# RasPiHAT-INPUT.net
KiCad netlist of a schematic drawn in Altium Designer
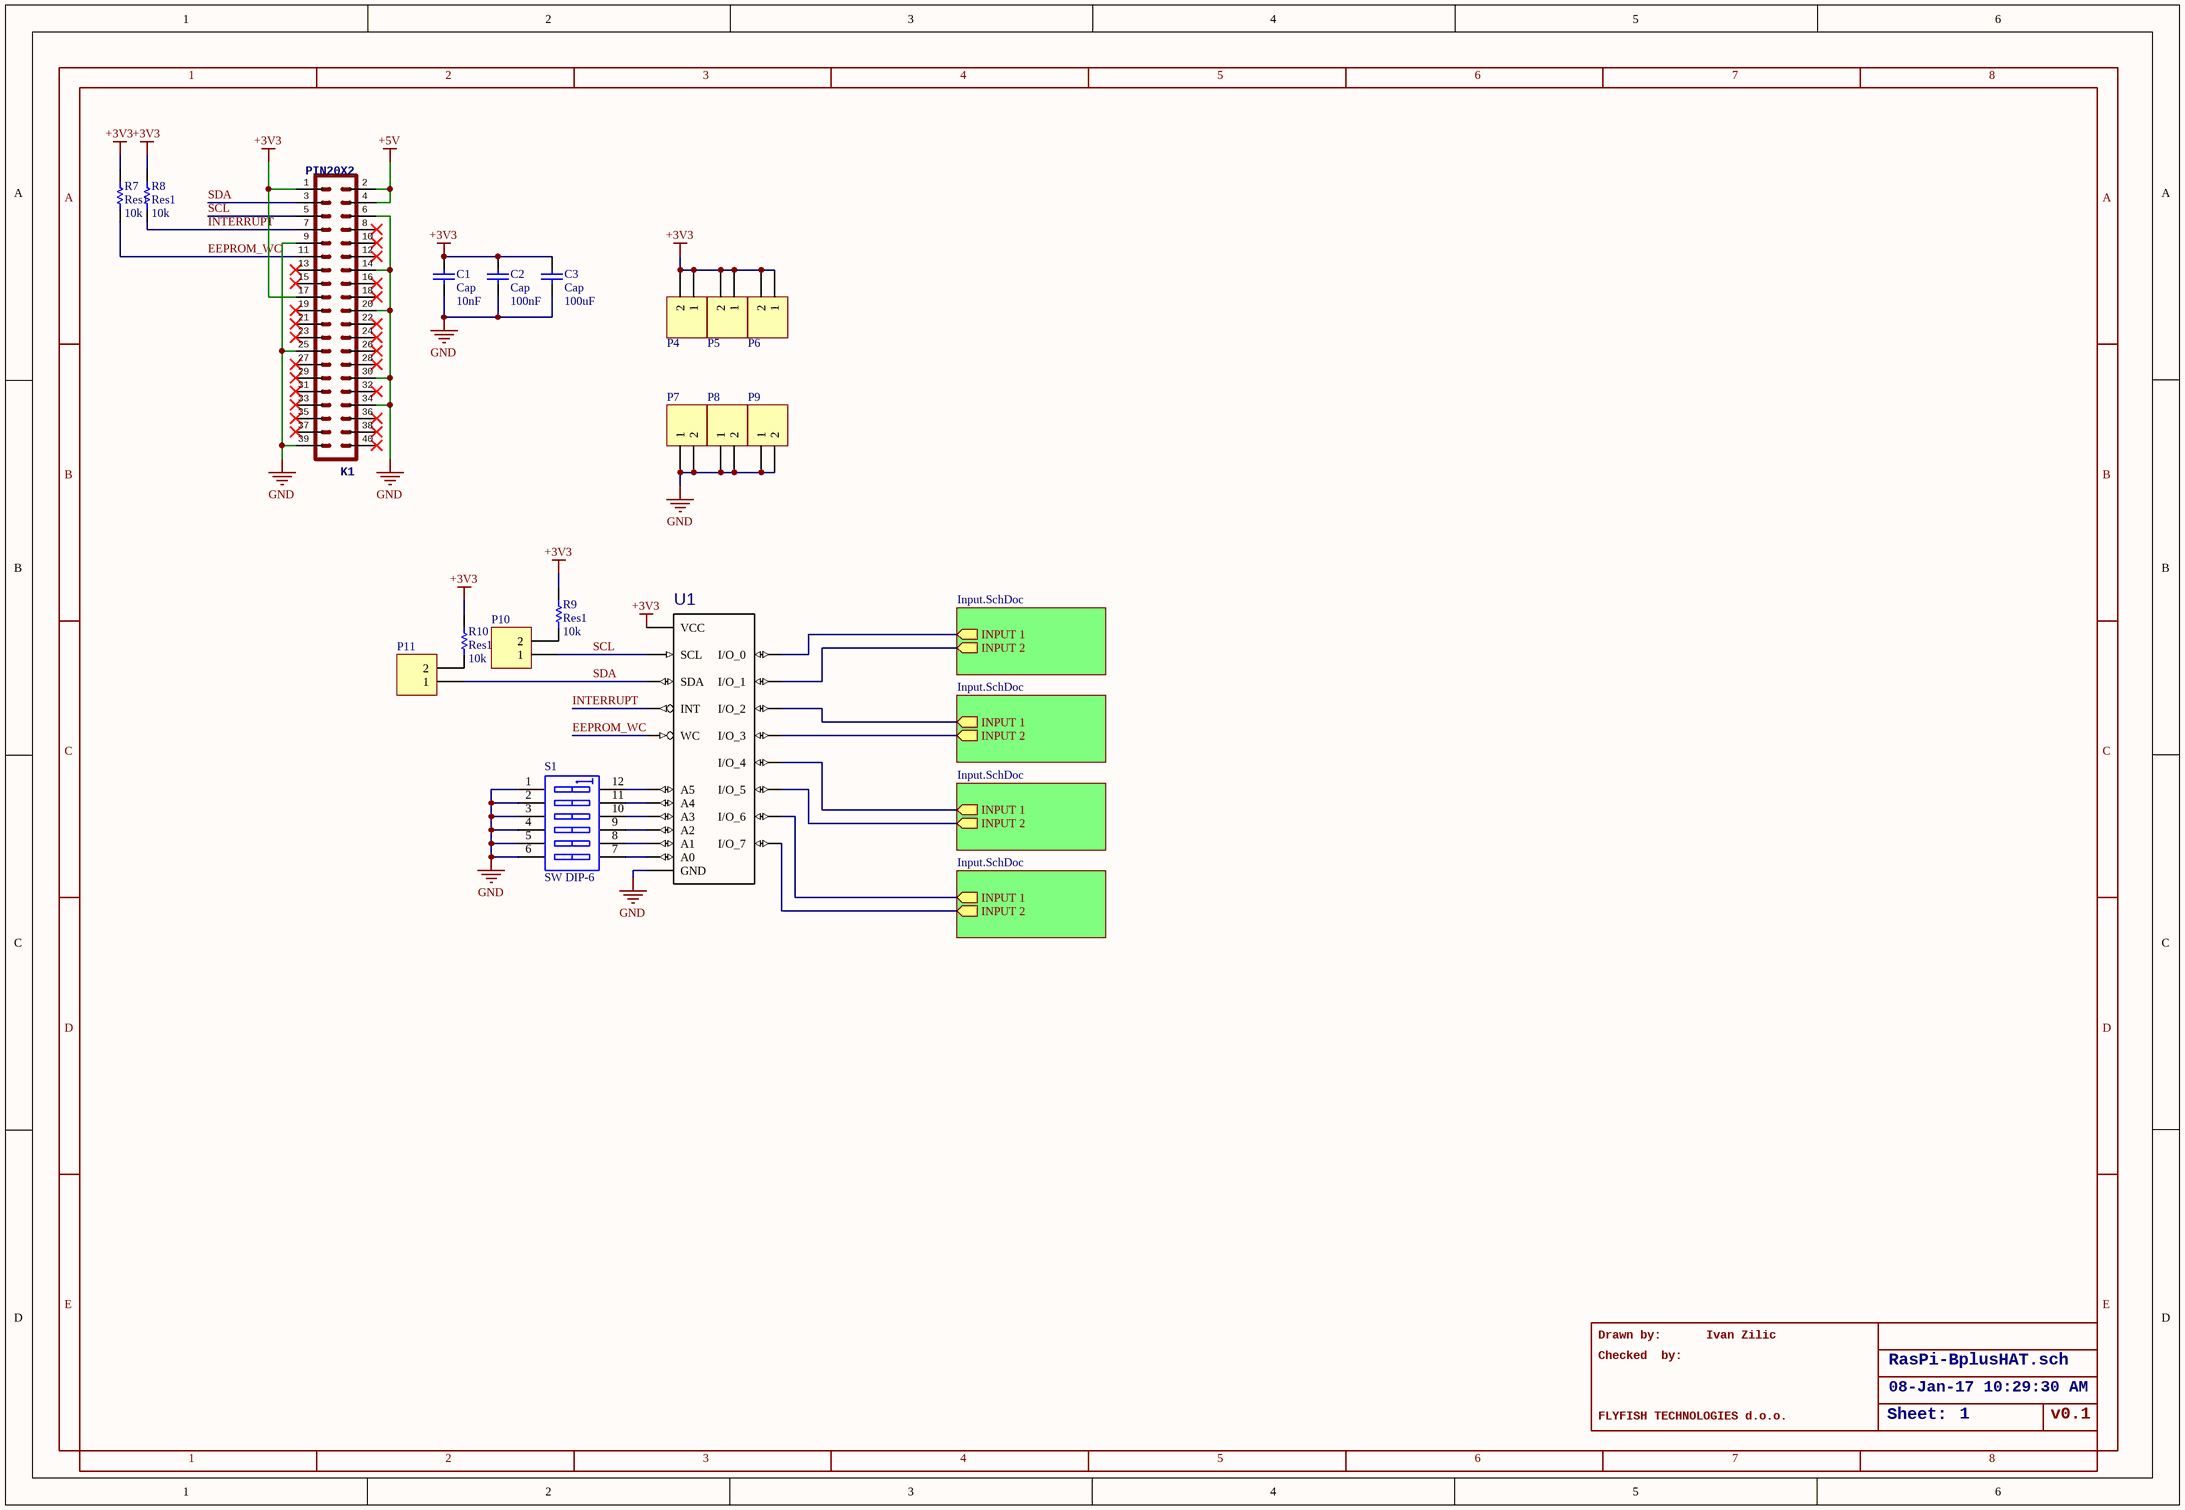
[diagram p0: RasPiHAT-INPUT.SchDoc]

(export (version "E")
  (design (tool "Eeschema 10.0.6"))
  (components
    (comp (ref "C1")
      (value "Cap")
      (footprint "6-0805_N")
      (description "Capacitor")
      (fields (field (name "ALTIUM_VALUE") "10nF") (field (name "PUBLISHER") "Altium Limited"))
      (libsource (lib "Miscellaneous Devices") (part "Cap"))
    )
    (comp (ref "C2")
      (value "Cap")
      (footprint "6-0805_N")
      (description "Capacitor")
      (fields (field (name "ALTIUM_VALUE") "100nF") (field (name "PUBLISHER") "Altium Limited"))
      (libsource (lib "Miscellaneous Devices") (part "Cap"))
    )
    (comp (ref "C3")
      (value "Cap")
      (footprint "6-0805_N")
      (description "Capacitor")
      (fields (field (name "ALTIUM_VALUE") "100uF") (field (name "PUBLISHER") "Altium Limited"))
      (libsource (lib "Miscellaneous Devices") (part "Cap"))
    )
    (comp (ref "K1")
      (value "PIN20X2")
      (footprint "HDR2X20")
      (fields (field (name ">VALUE") "PIN20X2") (field (name ">NAME") "K1"))
      (libsource (lib "FLYFISH") (part "PIN20X2"))
    )
    (comp (ref "P4")
      (value "Header 2")
      (footprint "2 PIN TERM BLK")
      (description "Header, 2-Pin")
      (fields (field (name "PUBLISHER") "Altium Limited"))
      (libsource (lib "") (part "Header 2_1"))
    )
    (comp (ref "P5")
      (value "Header 2")
      (footprint "2 PIN TERM BLK")
      (description "Header, 2-Pin")
      (fields (field (name "PUBLISHER") "Altium Limited"))
      (libsource (lib "") (part "Header 2_1"))
    )
    (comp (ref "P6")
      (value "Header 2")
      (footprint "2 PIN TERM BLK")
      (description "Header, 2-Pin")
      (fields (field (name "PUBLISHER") "Altium Limited"))
      (libsource (lib "") (part "Header 2_1"))
    )
    (comp (ref "P7")
      (value "Header 2")
      (footprint "2 PIN TERM BLK")
      (description "Header, 2-Pin")
      (fields (field (name "PUBLISHER") "Altium Limited"))
      (libsource (lib "Miscellaneous Connectors") (part "Header 2"))
    )
    (comp (ref "P8")
      (value "Header 2")
      (footprint "2 PIN TERM BLK")
      (description "Header, 2-Pin")
      (fields (field (name "PUBLISHER") "Altium Limited"))
      (libsource (lib "Miscellaneous Connectors") (part "Header 2"))
    )
    (comp (ref "P9")
      (value "Header 2")
      (footprint "2 PIN TERM BLK")
      (description "Header, 2-Pin")
      (fields (field (name "PUBLISHER") "Altium Limited"))
      (libsource (lib "Miscellaneous Connectors") (part "Header 2"))
    )
    (comp (ref "P10")
      (value "Header 2")
      (footprint "HDR1X2")
      (description "Header, 2-Pin")
      (fields (field (name "PUBLISHER") "Altium Limited"))
      (libsource (lib "") (part "Header 2_2"))
    )
    (comp (ref "P11")
      (value "Header 2")
      (footprint "HDR1X2")
      (description "Header, 2-Pin")
      (fields (field (name "PUBLISHER") "Altium Limited"))
      (libsource (lib "") (part "Header 2_2"))
    )
    (comp (ref "R7")
      (value "Res1")
      (footprint "6-0805_N")
      (description "Resistor")
      (fields (field (name "ALTIUM_VALUE") "10k") (field (name "PUBLISHER") "Altium Limited"))
      (libsource (lib "Miscellaneous Devices") (part "Res1"))
    )
    (comp (ref "R8")
      (value "Res1")
      (footprint "6-0805_N")
      (description "Resistor")
      (fields (field (name "ALTIUM_VALUE") "10k") (field (name "PUBLISHER") "Altium Limited"))
      (libsource (lib "Miscellaneous Devices") (part "Res1"))
    )
    (comp (ref "R9")
      (value "Res1")
      (footprint "6-0805_N")
      (description "Resistor")
      (fields (field (name "ALTIUM_VALUE") "10k") (field (name "PUBLISHER") "Altium Limited"))
      (libsource (lib "Miscellaneous Devices") (part "Res1"))
    )
    (comp (ref "R10")
      (value "Res1")
      (footprint "6-0805_N")
      (description "Resistor")
      (fields (field (name "ALTIUM_VALUE") "10k") (field (name "PUBLISHER") "Altium Limited"))
      (libsource (lib "Miscellaneous Devices") (part "Res1"))
    )
    (comp (ref "S1")
      (value "SW DIP-6")
      (footprint "DIP-12/SW")
      (description "DIP Switch, 6 Position, SPST")
      (fields (field (name "PUBLISHER") "Altium Limited"))
      (libsource (lib "Miscellaneous Devices") (part "SW DIP-6"))
    )
    (comp (ref "U1")
      (value "PCA9501")
      (footprint "TSSOP20")
      (fields (field (name "MF") "NXP Semiconductors"))
      (libsource (lib "PCA9501") (part "PCA9501"))
    )
  )
  (nets
    (net (code "1") (name "+3V3") (class "Default")
      (node (ref "C1") (pin "2") (pinfunction "2_2") (pintype "passive"))
      (node (ref "C2") (pin "2") (pinfunction "2_2") (pintype "passive"))
      (node (ref "C3") (pin "2") (pinfunction "2_2") (pintype "passive"))
      (node (ref "K1") (pin "1") (pinfunction "1_1") (pintype "passive"))
      (node (ref "K1") (pin "17") (pinfunction "17_17") (pintype "passive"))
      (node (ref "P4") (pin "1") (pinfunction "1_1") (pintype "passive"))
      (node (ref "P4") (pin "2") (pinfunction "2_2") (pintype "passive"))
      (node (ref "P5") (pin "1") (pinfunction "1_1") (pintype "passive"))
      (node (ref "P5") (pin "2") (pinfunction "2_2") (pintype "passive"))
      (node (ref "P6") (pin "1") (pinfunction "1_1") (pintype "passive"))
      (node (ref "P6") (pin "2") (pinfunction "2_2") (pintype "passive"))
      (node (ref "R10") (pin "1") (pinfunction "1_1") (pintype "passive"))
      (node (ref "R7") (pin "1") (pinfunction "1_1") (pintype "passive"))
      (node (ref "R8") (pin "1") (pinfunction "1_1") (pintype "passive"))
      (node (ref "R9") (pin "1") (pinfunction "1_1") (pintype "passive"))
      (node (ref "U1") (pin "20") (pinfunction "VCC_20") (pintype "power_in"))
    )
    (net (code "2") (name "+5V") (class "Default")
      (node (ref "K1") (pin "2") (pinfunction "2_2") (pintype "passive"))
      (node (ref "K1") (pin "4") (pinfunction "4_4") (pintype "passive"))
    )
    (net (code "3") (name "/EEPROM_WC") (class "Default")
      (node (ref "K1") (pin "11") (pinfunction "11_11") (pintype "passive"))
      (node (ref "R7") (pin "2") (pinfunction "2_2") (pintype "passive"))
      (node (ref "U1") (pin "17") (pinfunction "WC_17") (pintype "input"))
    )
    (net (code "4") (name "/INPUT 1") (class "Default")
      (node (ref "U1") (pin "6") (pinfunction "I/O_2_6") (pintype "bidirectional"))
    )
    (net (code "5") (name "/INPUT 1_1") (class "Default")
      (node (ref "U1") (pin "13") (pinfunction "I/O_4_13") (pintype "bidirectional"))
    )
    (net (code "6") (name "/INPUT 1_2") (class "Default")
      (node (ref "U1") (pin "4") (pinfunction "I/O_0_4") (pintype "bidirectional"))
    )
    (net (code "7") (name "/INPUT 1_3") (class "Default")
      (node (ref "U1") (pin "15") (pinfunction "I/O_6_15") (pintype "bidirectional"))
    )
    (net (code "8") (name "/INPUT 2") (class "Default")
      (node (ref "U1") (pin "7") (pinfunction "I/O_3_7") (pintype "bidirectional"))
    )
    (net (code "9") (name "/INPUT 2_1") (class "Default")
      (node (ref "U1") (pin "5") (pinfunction "I/O_1_5") (pintype "bidirectional"))
    )
    (net (code "10") (name "/INPUT 2_2") (class "Default")
      (node (ref "U1") (pin "14") (pinfunction "I/O_5_14") (pintype "bidirectional"))
    )
    (net (code "11") (name "/INPUT 2_3") (class "Default")
      (node (ref "U1") (pin "16") (pinfunction "I/O_7_16") (pintype "bidirectional"))
    )
    (net (code "12") (name "/INTERRUPT") (class "Default")
      (node (ref "K1") (pin "7") (pinfunction "7_7") (pintype "passive"))
      (node (ref "R8") (pin "2") (pinfunction "2_2") (pintype "passive"))
      (node (ref "U1") (pin "8") (pinfunction "INT_8") (pintype "output"))
    )
    (net (code "13") (name "/SCL") (class "Default")
      (node (ref "K1") (pin "5") (pinfunction "5_5") (pintype "passive"))
      (node (ref "P10") (pin "1") (pinfunction "1_1") (pintype "passive"))
      (node (ref "U1") (pin "18") (pinfunction "SCL_18") (pintype "input"))
    )
    (net (code "14") (name "/SDA") (class "Default")
      (node (ref "K1") (pin "3") (pinfunction "3_3") (pintype "passive"))
      (node (ref "P11") (pin "1") (pinfunction "1_1") (pintype "passive"))
      (node (ref "U1") (pin "19") (pinfunction "SDA_19") (pintype "bidirectional"))
    )
    (net (code "15") (name "GND") (class "Default")
      (node (ref "C1") (pin "1") (pinfunction "1_1") (pintype "passive"))
      (node (ref "C2") (pin "1") (pinfunction "1_1") (pintype "passive"))
      (node (ref "C3") (pin "1") (pinfunction "1_1") (pintype "passive"))
      (node (ref "K1") (pin "14") (pinfunction "14_14") (pintype "passive"))
      (node (ref "K1") (pin "20") (pinfunction "20_20") (pintype "passive"))
      (node (ref "K1") (pin "25") (pinfunction "25_25") (pintype "passive"))
      (node (ref "K1") (pin "30") (pinfunction "30_30") (pintype "passive"))
      (node (ref "K1") (pin "34") (pinfunction "34_34") (pintype "passive"))
      (node (ref "K1") (pin "39") (pinfunction "39_39") (pintype "passive"))
      (node (ref "K1") (pin "6") (pinfunction "6_6") (pintype "passive"))
      (node (ref "K1") (pin "9") (pinfunction "9_9") (pintype "passive"))
      (node (ref "P7") (pin "1") (pinfunction "1_1") (pintype "passive"))
      (node (ref "P7") (pin "2") (pinfunction "2_2") (pintype "passive"))
      (node (ref "P8") (pin "1") (pinfunction "1_1") (pintype "passive"))
      (node (ref "P8") (pin "2") (pinfunction "2_2") (pintype "passive"))
      (node (ref "P9") (pin "1") (pinfunction "1_1") (pintype "passive"))
      (node (ref "P9") (pin "2") (pinfunction "2_2") (pintype "passive"))
      (node (ref "S1") (pin "1") (pinfunction "A1_1") (pintype "passive"))
      (node (ref "S1") (pin "2") (pinfunction "A2_2") (pintype "passive"))
      (node (ref "S1") (pin "3") (pinfunction "A3_3") (pintype "passive"))
      (node (ref "S1") (pin "4") (pinfunction "A4_4") (pintype "passive"))
      (node (ref "S1") (pin "5") (pinfunction "A5_5") (pintype "passive"))
      (node (ref "S1") (pin "6") (pinfunction "A6_6") (pintype "passive"))
      (node (ref "U1") (pin "10") (pinfunction "GND_10") (pintype "power_in"))
    )
    (net (code "16") (name "Net-(P10-Pad2)") (class "Default")
      (node (ref "P10") (pin "2") (pinfunction "2_2") (pintype "passive"))
      (node (ref "R9") (pin "2") (pinfunction "2_2") (pintype "passive"))
    )
    (net (code "17") (name "Net-(P11-Pad2)") (class "Default")
      (node (ref "P11") (pin "2") (pinfunction "2_2") (pintype "passive"))
      (node (ref "R10") (pin "2") (pinfunction "2_2") (pintype "passive"))
    )
    (net (code "18") (name "Net-(S1-B1)") (class "Default")
      (node (ref "S1") (pin "12") (pinfunction "B1_12") (pintype "passive"))
      (node (ref "U1") (pin "9") (pinfunction "A5_9") (pintype "bidirectional"))
    )
    (net (code "19") (name "Net-(S1-B2)") (class "Default")
      (node (ref "S1") (pin "11") (pinfunction "B2_11") (pintype "passive"))
      (node (ref "U1") (pin "11") (pinfunction "A4_11") (pintype "bidirectional"))
    )
    (net (code "20") (name "Net-(S1-B3)") (class "Default")
      (node (ref "S1") (pin "10") (pinfunction "B3_10") (pintype "passive"))
      (node (ref "U1") (pin "12") (pinfunction "A3_12") (pintype "bidirectional"))
    )
    (net (code "21") (name "Net-(S1-B4)") (class "Default")
      (node (ref "S1") (pin "9") (pinfunction "B4_9") (pintype "passive"))
      (node (ref "U1") (pin "3") (pinfunction "A2_3") (pintype "bidirectional"))
    )
    (net (code "22") (name "Net-(S1-B5)") (class "Default")
      (node (ref "S1") (pin "8") (pinfunction "B5_8") (pintype "passive"))
      (node (ref "U1") (pin "2") (pinfunction "A1_2") (pintype "bidirectional"))
    )
    (net (code "23") (name "Net-(S1-B6)") (class "Default")
      (node (ref "S1") (pin "7") (pinfunction "B6_7") (pintype "passive"))
      (node (ref "U1") (pin "1") (pinfunction "A0_1") (pintype "bidirectional"))
    )
    (net (code "24") (name "unconnected-(K1-Pad8)") (class "Default")
      (node (ref "K1") (pin "8") (pinfunction "8_8") (pintype "passive+no_connect"))
    )
    (net (code "25") (name "unconnected-(K1-Pad10)") (class "Default")
      (node (ref "K1") (pin "10") (pinfunction "10_10") (pintype "passive+no_connect"))
    )
    (net (code "26") (name "unconnected-(K1-Pad12)") (class "Default")
      (node (ref "K1") (pin "12") (pinfunction "12_12") (pintype "passive+no_connect"))
    )
    (net (code "27") (name "unconnected-(K1-Pad13)") (class "Default")
      (node (ref "K1") (pin "13") (pinfunction "13_13") (pintype "passive+no_connect"))
    )
    (net (code "28") (name "unconnected-(K1-Pad15)") (class "Default")
      (node (ref "K1") (pin "15") (pinfunction "15_15") (pintype "passive+no_connect"))
    )
    (net (code "29") (name "unconnected-(K1-Pad16)") (class "Default")
      (node (ref "K1") (pin "16") (pinfunction "16_16") (pintype "passive+no_connect"))
    )
    (net (code "30") (name "unconnected-(K1-Pad18)") (class "Default")
      (node (ref "K1") (pin "18") (pinfunction "18_18") (pintype "passive+no_connect"))
    )
    (net (code "31") (name "unconnected-(K1-Pad19)") (class "Default")
      (node (ref "K1") (pin "19") (pinfunction "19_19") (pintype "passive+no_connect"))
    )
    (net (code "32") (name "unconnected-(K1-Pad21)") (class "Default")
      (node (ref "K1") (pin "21") (pinfunction "21_21") (pintype "passive+no_connect"))
    )
    (net (code "33") (name "unconnected-(K1-Pad22)") (class "Default")
      (node (ref "K1") (pin "22") (pinfunction "22_22") (pintype "passive+no_connect"))
    )
    (net (code "34") (name "unconnected-(K1-Pad23)") (class "Default")
      (node (ref "K1") (pin "23") (pinfunction "23_23") (pintype "passive+no_connect"))
    )
    (net (code "35") (name "unconnected-(K1-Pad24)") (class "Default")
      (node (ref "K1") (pin "24") (pinfunction "24_24") (pintype "passive+no_connect"))
    )
    (net (code "36") (name "unconnected-(K1-Pad26)") (class "Default")
      (node (ref "K1") (pin "26") (pinfunction "26_26") (pintype "passive+no_connect"))
    )
    (net (code "37") (name "unconnected-(K1-Pad27)") (class "Default")
      (node (ref "K1") (pin "27") (pinfunction "27_27") (pintype "passive+no_connect"))
    )
    (net (code "38") (name "unconnected-(K1-Pad28)") (class "Default")
      (node (ref "K1") (pin "28") (pinfunction "28_28") (pintype "passive+no_connect"))
    )
    (net (code "39") (name "unconnected-(K1-Pad29)") (class "Default")
      (node (ref "K1") (pin "29") (pinfunction "29_29") (pintype "passive+no_connect"))
    )
    (net (code "40") (name "unconnected-(K1-Pad31)") (class "Default")
      (node (ref "K1") (pin "31") (pinfunction "31_31") (pintype "passive+no_connect"))
    )
    (net (code "41") (name "unconnected-(K1-Pad32)") (class "Default")
      (node (ref "K1") (pin "32") (pinfunction "32_32") (pintype "passive+no_connect"))
    )
    (net (code "42") (name "unconnected-(K1-Pad33)") (class "Default")
      (node (ref "K1") (pin "33") (pinfunction "33_33") (pintype "passive+no_connect"))
    )
    (net (code "43") (name "unconnected-(K1-Pad35)") (class "Default")
      (node (ref "K1") (pin "35") (pinfunction "35_35") (pintype "passive+no_connect"))
    )
    (net (code "44") (name "unconnected-(K1-Pad36)") (class "Default")
      (node (ref "K1") (pin "36") (pinfunction "36_36") (pintype "passive+no_connect"))
    )
    (net (code "45") (name "unconnected-(K1-Pad37)") (class "Default")
      (node (ref "K1") (pin "37") (pinfunction "37_37") (pintype "passive+no_connect"))
    )
    (net (code "46") (name "unconnected-(K1-Pad38)") (class "Default")
      (node (ref "K1") (pin "38") (pinfunction "38_38") (pintype "passive+no_connect"))
    )
    (net (code "47") (name "unconnected-(K1-Pad40)") (class "Default")
      (node (ref "K1") (pin "40") (pinfunction "40_40") (pintype "passive+no_connect"))
    )
  )
)
